# PMIC.net
KiCad netlist of a schematic drawn in Altium Designer
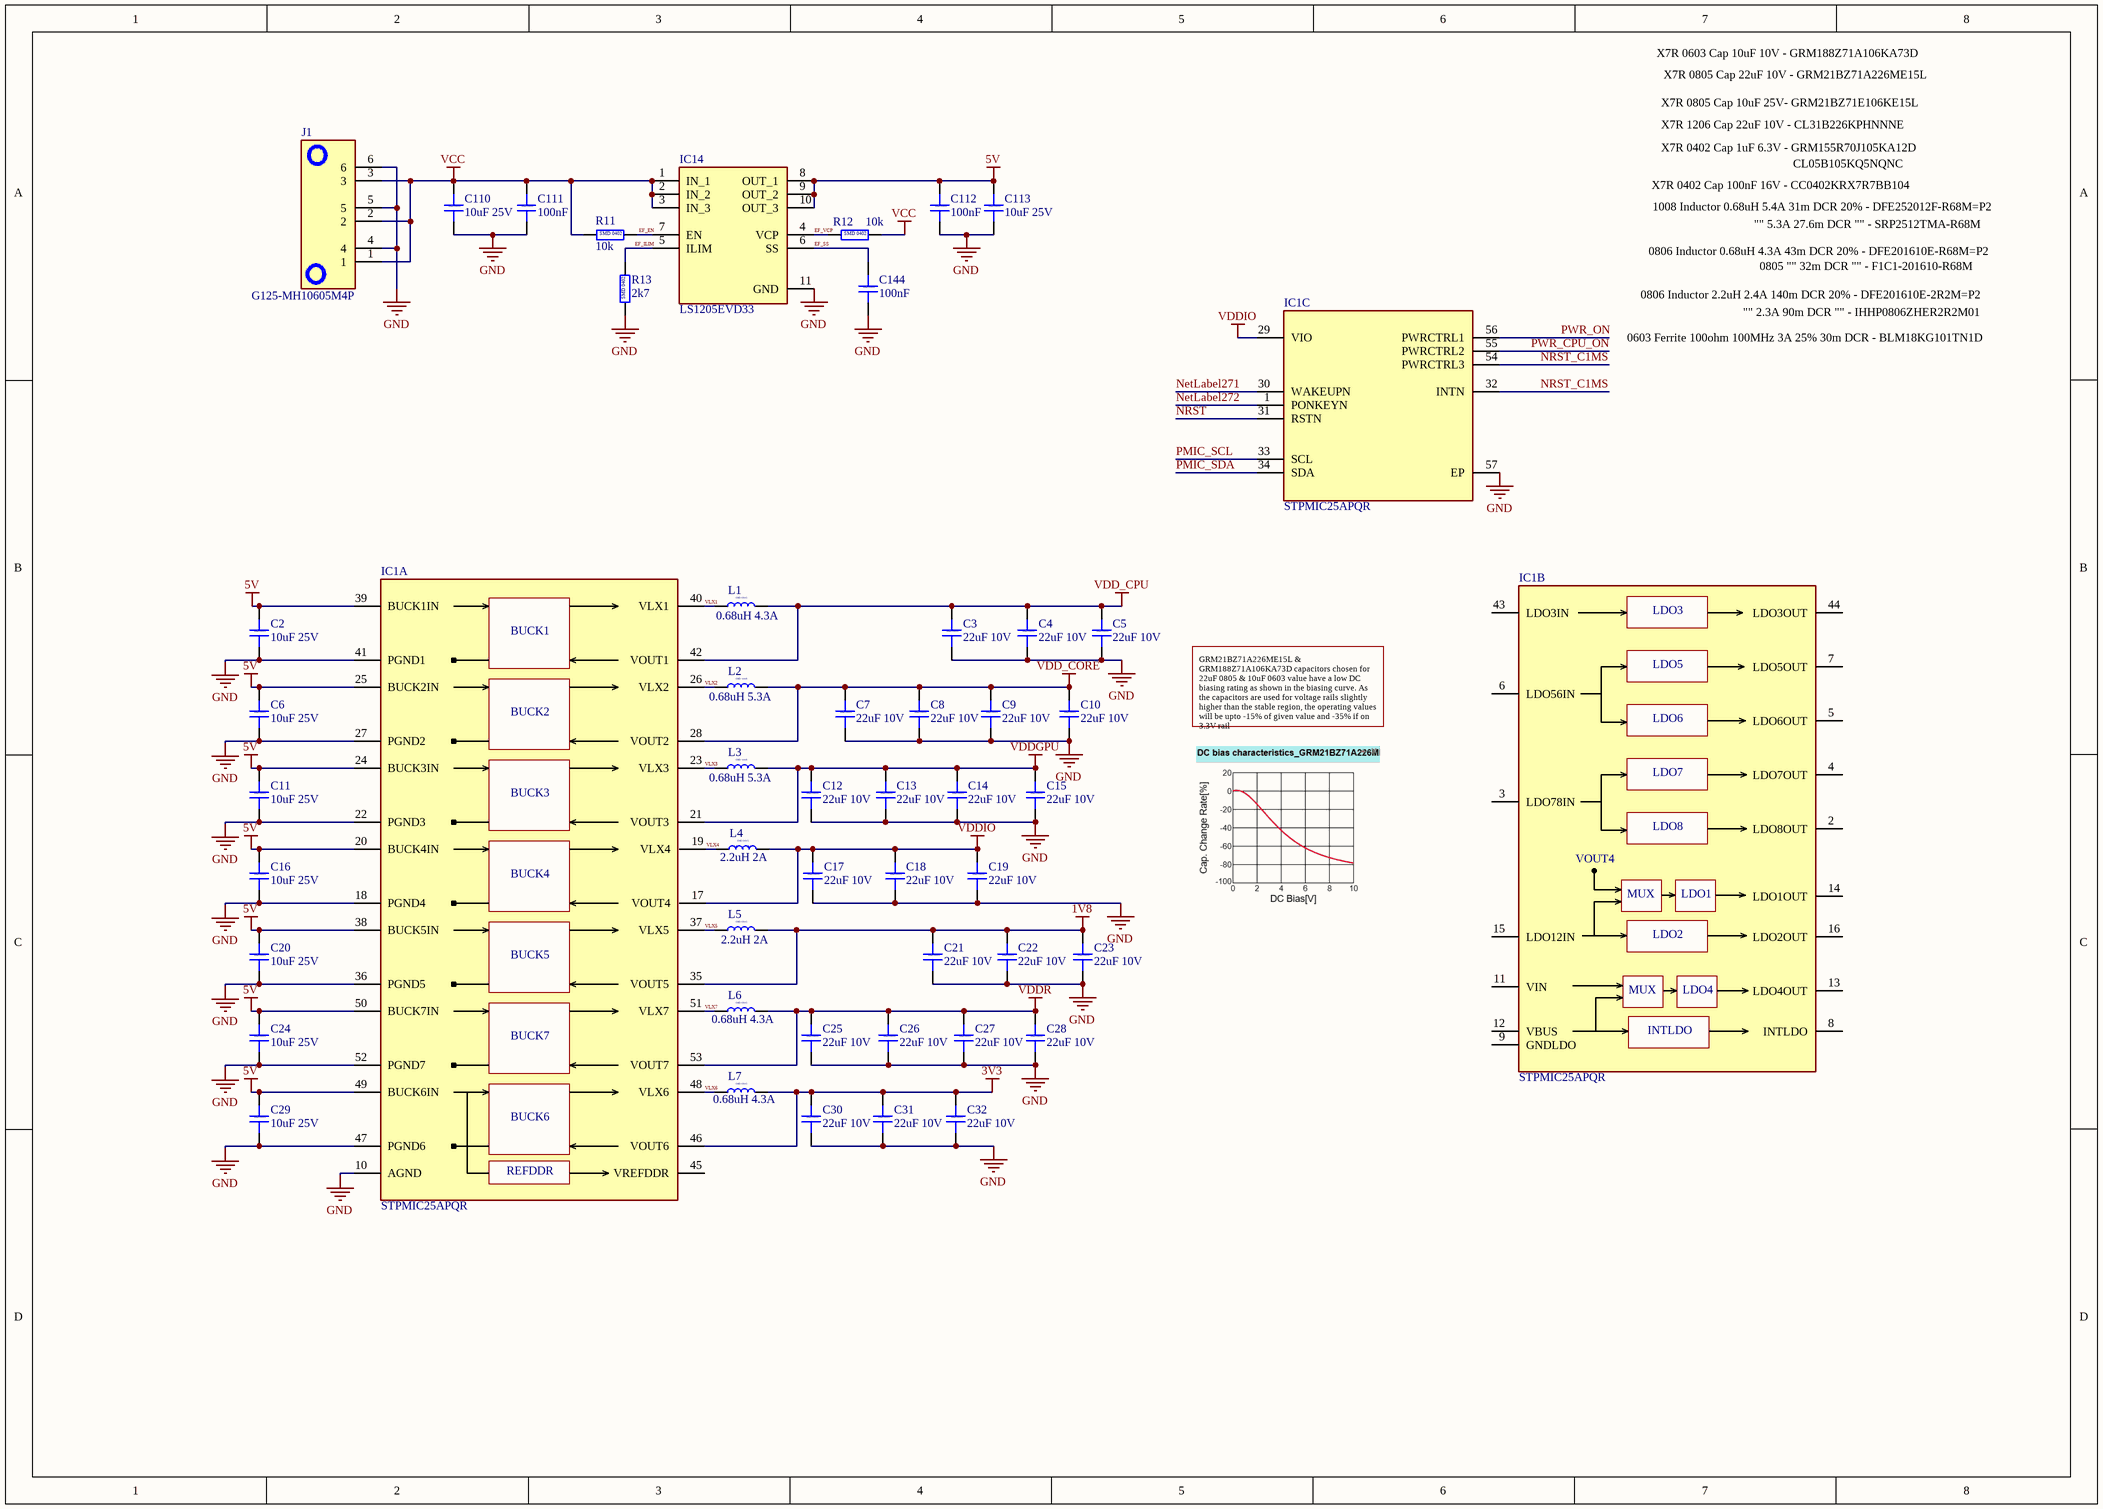
[diagram p0: PMIC.SchDoc]

(export (version "E")
  (design (tool "Eeschema 10.0.6"))
  (components
    (comp (ref "C2")
      (value "10uF 25V")
      (footprint "CAP_0805")
      (description "Capacitor SMD 0805 RATED")
      (libsource (lib "STeRG-Passives-Standard") (part "Capacitor-SMD-0805"))
    )
    (comp (ref "C3")
      (value "22uF 10V")
      (footprint "CAP_0805")
      (description "Capacitor SMD 0805 RATED")
      (libsource (lib "STeRG-Passives-Standard") (part "Capacitor-SMD-0805"))
    )
    (comp (ref "C4")
      (value "22uF 10V")
      (footprint "CAP_0805")
      (description "Capacitor SMD 0805 RATED")
      (libsource (lib "STeRG-Passives-Standard") (part "Capacitor-SMD-0805"))
    )
    (comp (ref "C5")
      (value "22uF 10V")
      (footprint "CAP_0805")
      (description "Capacitor SMD 0805 RATED")
      (libsource (lib "STeRG-Passives-Standard") (part "Capacitor-SMD-0805"))
    )
    (comp (ref "C6")
      (value "10uF 25V")
      (footprint "CAP_0805")
      (description "Capacitor SMD 0805 RATED")
      (libsource (lib "STeRG-Passives-Standard") (part "Capacitor-SMD-0805"))
    )
    (comp (ref "C7")
      (value "22uF 10V")
      (footprint "CAP_0805")
      (description "Capacitor SMD 0805 RATED")
      (libsource (lib "STeRG-Passives-Standard") (part "Capacitor-SMD-0805"))
    )
    (comp (ref "C8")
      (value "22uF 10V")
      (footprint "CAP_0805")
      (description "Capacitor SMD 0805 RATED")
      (libsource (lib "STeRG-Passives-Standard") (part "Capacitor-SMD-0805"))
    )
    (comp (ref "C9")
      (value "22uF 10V")
      (footprint "CAP_0805")
      (description "Capacitor SMD 0805 RATED")
      (libsource (lib "STeRG-Passives-Standard") (part "Capacitor-SMD-0805"))
    )
    (comp (ref "C10")
      (value "22uF 10V")
      (footprint "CAP_0805")
      (description "Capacitor SMD 0805 RATED")
      (libsource (lib "STeRG-Passives-Standard") (part "Capacitor-SMD-0805"))
    )
    (comp (ref "C11")
      (value "10uF 25V")
      (footprint "CAP_0805")
      (description "Capacitor SMD 0805 RATED")
      (libsource (lib "STeRG-Passives-Standard") (part "Capacitor-SMD-0805"))
    )
    (comp (ref "C12")
      (value "22uF 10V")
      (footprint "CAP_0805")
      (description "Capacitor SMD 0805 RATED")
      (libsource (lib "STeRG-Passives-Standard") (part "Capacitor-SMD-0805"))
    )
    (comp (ref "C13")
      (value "22uF 10V")
      (footprint "CAP_0805")
      (description "Capacitor SMD 0805 RATED")
      (libsource (lib "STeRG-Passives-Standard") (part "Capacitor-SMD-0805"))
    )
    (comp (ref "C14")
      (value "22uF 10V")
      (footprint "CAP_0805")
      (description "Capacitor SMD 0805 RATED")
      (libsource (lib "STeRG-Passives-Standard") (part "Capacitor-SMD-0805"))
    )
    (comp (ref "C15")
      (value "22uF 10V")
      (footprint "CAP_0805")
      (description "Capacitor SMD 0805 RATED")
      (libsource (lib "STeRG-Passives-Standard") (part "Capacitor-SMD-0805"))
    )
    (comp (ref "C16")
      (value "10uF 25V")
      (footprint "CAP_0805")
      (description "Capacitor SMD 0805 RATED")
      (libsource (lib "STeRG-Passives-Standard") (part "Capacitor-SMD-0805"))
    )
    (comp (ref "C17")
      (value "22uF 10V")
      (footprint "CAP_0805")
      (description "Capacitor SMD 0805 RATED")
      (libsource (lib "STeRG-Passives-Standard") (part "Capacitor-SMD-0805"))
    )
    (comp (ref "C18")
      (value "22uF 10V")
      (footprint "CAP_0805")
      (description "Capacitor SMD 0805 RATED")
      (libsource (lib "STeRG-Passives-Standard") (part "Capacitor-SMD-0805"))
    )
    (comp (ref "C19")
      (value "22uF 10V")
      (footprint "CAP_0805")
      (description "Capacitor SMD 0805 RATED")
      (libsource (lib "STeRG-Passives-Standard") (part "Capacitor-SMD-0805"))
    )
    (comp (ref "C20")
      (value "10uF 25V")
      (footprint "CAP_0805")
      (description "Capacitor SMD 0805 RATED")
      (libsource (lib "STeRG-Passives-Standard") (part "Capacitor-SMD-0805"))
    )
    (comp (ref "C21")
      (value "22uF 10V")
      (footprint "CAP_0805")
      (description "Capacitor SMD 0805 RATED")
      (libsource (lib "STeRG-Passives-Standard") (part "Capacitor-SMD-0805"))
    )
    (comp (ref "C22")
      (value "22uF 10V")
      (footprint "CAP_0805")
      (description "Capacitor SMD 0805 RATED")
      (libsource (lib "STeRG-Passives-Standard") (part "Capacitor-SMD-0805"))
    )
    (comp (ref "C23")
      (value "22uF 10V")
      (footprint "CAP_0805")
      (description "Capacitor SMD 0805 RATED")
      (libsource (lib "STeRG-Passives-Standard") (part "Capacitor-SMD-0805"))
    )
    (comp (ref "C24")
      (value "10uF 25V")
      (footprint "CAP_0805")
      (description "Capacitor SMD 0805 RATED")
      (libsource (lib "STeRG-Passives-Standard") (part "Capacitor-SMD-0805"))
    )
    (comp (ref "C25")
      (value "22uF 10V")
      (footprint "CAP_0805")
      (description "Capacitor SMD 0805 RATED")
      (libsource (lib "STeRG-Passives-Standard") (part "Capacitor-SMD-0805"))
    )
    (comp (ref "C26")
      (value "22uF 10V")
      (footprint "CAP_0805")
      (description "Capacitor SMD 0805 RATED")
      (libsource (lib "STeRG-Passives-Standard") (part "Capacitor-SMD-0805"))
    )
    (comp (ref "C27")
      (value "22uF 10V")
      (footprint "CAP_0805")
      (description "Capacitor SMD 0805 RATED")
      (libsource (lib "STeRG-Passives-Standard") (part "Capacitor-SMD-0805"))
    )
    (comp (ref "C28")
      (value "22uF 10V")
      (footprint "CAP_0805")
      (description "Capacitor SMD 0805 RATED")
      (libsource (lib "STeRG-Passives-Standard") (part "Capacitor-SMD-0805"))
    )
    (comp (ref "C29")
      (value "10uF 25V")
      (footprint "CAP_0805")
      (description "Capacitor SMD 0805 RATED")
      (libsource (lib "STeRG-Passives-Standard") (part "Capacitor-SMD-0805"))
    )
    (comp (ref "C30")
      (value "22uF 10V")
      (footprint "CAP_0805")
      (description "Capacitor SMD 0805 RATED")
      (libsource (lib "STeRG-Passives-Standard") (part "Capacitor-SMD-0805"))
    )
    (comp (ref "C31")
      (value "22uF 10V")
      (footprint "CAP_0805")
      (description "Capacitor SMD 0805 RATED")
      (libsource (lib "STeRG-Passives-Standard") (part "Capacitor-SMD-0805"))
    )
    (comp (ref "C32")
      (value "22uF 10V")
      (footprint "CAP_0805")
      (description "Capacitor SMD 0805 RATED")
      (libsource (lib "STeRG-Passives-Standard") (part "Capacitor-SMD-0805"))
    )
    (comp (ref "C110")
      (value "10uF 25V")
      (footprint "CAP_0805")
      (description "Capacitor SMD 0805 RATED")
      (libsource (lib "STeRG-Passives-Standard") (part "Capacitor-SMD-0805"))
    )
    (comp (ref "C111")
      (value "100nF")
      (footprint "CAP_0402")
      (description "Capacitor SMD 0402 RATED")
      (libsource (lib "STeRG-Passives-Standard") (part "Capacitor-SMD-0402"))
    )
    (comp (ref "C112")
      (value "100nF")
      (footprint "CAP_0402")
      (description "Capacitor SMD 0402 RATED")
      (libsource (lib "STeRG-Passives-Standard") (part "Capacitor-SMD-0402"))
    )
    (comp (ref "C113")
      (value "10uF 25V")
      (footprint "CAP_0805")
      (description "Capacitor SMD 0805 RATED")
      (libsource (lib "STeRG-Passives-Standard") (part "Capacitor-SMD-0805"))
    )
    (comp (ref "C144")
      (value "100nF")
      (footprint "CAP_0402")
      (description "Capacitor SMD 0402 RATED")
      (libsource (lib "STeRG-Passives-Standard") (part "Capacitor-SMD-0402"))
    )
    (comp (ref "IC1")
      (value "STPMIC25APQR")
      (footprint "QFN40P650X650X90-57N-D")
      (description "Integrated Circuit")
      (fields (field (name "MOUSER PART NUMBER") "511-STPMIC25APQR"))
      (libsource (lib "STeRG-ICs-Standard") (part "STPMIC25APQR"))
    )
    (comp (ref "IC14")
      (value "LS1205EVD33")
      (footprint "SamacSys:LS1205EVD33")
      (description "Integrated Circuit")
      (fields (field (name "MOUSER PART NUMBER") "576-LS1205EVD33"))
      (libsource (lib "STeRG-Passives-Standard") (part "LS1205EVD33"))
    )
    (comp (ref "J1")
      (value "G125-MH10605M4P")
      (footprint "G125-MH10605M4P_1")
      (description "Connector")
      (fields (field (name "MOUSER PART NUMBER") "855-G125MH1065M4PM4P"))
      (libsource (lib "STeRG-Passives-Standard") (part "G125-MH10605M4P"))
    )
    (comp (ref "L1")
      (value "0.68uH 4.3A")
      (footprint "DFE2HCAH1R0MJ0L")
      (description "Inductor SMD 0805")
      (libsource (lib "STeRG-Passives-Standard") (part "Inductor-SMD-RF-0806/0805"))
    )
    (comp (ref "L2")
      (value "0.68uH 5.3A")
      (footprint "1285ASH1R0MP2")
      (description "Inductor SMD 1008")
      (libsource (lib "STeRG-Passives-Standard") (part "Inductor-SMD-RF-1008"))
    )
    (comp (ref "L3")
      (value "0.68uH 5.3A")
      (footprint "1285ASH1R0MP2")
      (description "Inductor SMD 1008")
      (libsource (lib "STeRG-Passives-Standard") (part "Inductor-SMD-RF-1008"))
    )
    (comp (ref "L4")
      (value "2.2uH 2A")
      (footprint "DFE2HCAH1R0MJ0L")
      (description "Inductor SMD 0805")
      (libsource (lib "STeRG-Passives-Standard") (part "Inductor-SMD-RF-0806/0805"))
    )
    (comp (ref "L5")
      (value "2.2uH 2A")
      (footprint "DFE2HCAH1R0MJ0L")
      (description "Inductor SMD 0805")
      (libsource (lib "STeRG-Passives-Standard") (part "Inductor-SMD-RF-0806/0805"))
    )
    (comp (ref "L6")
      (value "0.68uH 4.3A")
      (footprint "DFE2HCAH1R0MJ0L")
      (description "Inductor SMD 0805")
      (libsource (lib "STeRG-Passives-Standard") (part "Inductor-SMD-RF-0806/0805"))
    )
    (comp (ref "L7")
      (value "0.68uH 4.3A")
      (footprint "DFE2HCAH1R0MJ0L")
      (description "Inductor SMD 0805")
      (libsource (lib "STeRG-Passives-Standard") (part "Inductor-SMD-RF-0806/0805"))
    )
    (comp (ref "R11")
      (value "10k")
      (footprint "RES_0402")
      (description "Resistor SMD 0402 RATED")
      (libsource (lib "STeRG-Passives-Standard") (part "Resistor-SMD-0402"))
    )
    (comp (ref "R12")
      (value "10k")
      (footprint "RES_0402")
      (description "Resistor SMD 0402 RATED")
      (libsource (lib "STeRG-Passives-Standard") (part "Resistor-SMD-0402"))
    )
    (comp (ref "R13")
      (value "2k7")
      (footprint "RES_0402")
      (description "Resistor SMD 0402 RATED")
      (libsource (lib "STeRG-Passives-Standard") (part "Resistor-SMD-0402"))
    )
  )
  (nets
    (net (code "1") (name "/EF_EN") (class "Default")
      (node (ref "IC14") (pin "7") (pinfunction "EN_7") (pintype "passive"))
      (node (ref "R11") (pin "2") (pinfunction "2_2") (pintype "passive"))
    )
    (net (code "2") (name "/EF_ILIM") (class "Default")
      (node (ref "IC14") (pin "5") (pinfunction "ILIM_5") (pintype "passive"))
      (node (ref "R13") (pin "2") (pinfunction "2_2") (pintype "passive"))
    )
    (net (code "3") (name "/EF_SS") (class "Default")
      (node (ref "C144") (pin "1") (pinfunction "1_1") (pintype "passive"))
      (node (ref "IC14") (pin "6") (pinfunction "SS_6") (pintype "passive"))
    )
    (net (code "4") (name "/EF_VCP") (class "Default")
      (node (ref "IC14") (pin "4") (pinfunction "VCP_4") (pintype "passive"))
      (node (ref "R12") (pin "1") (pinfunction "1_1") (pintype "passive"))
    )
    (net (code "5") (name "/NRST") (class "Default")
      (node (ref "IC1") (pin "31") (pinfunction "RSTN_31") (pintype "passive"))
    )
    (net (code "6") (name "/NRST_C1MS") (class "Default")
      (node (ref "IC1") (pin "32") (pinfunction "INTN_32") (pintype "passive"))
      (node (ref "IC1") (pin "54") (pinfunction "PWRCTRL3_54") (pintype "passive"))
    )
    (net (code "7") (name "/NetLabel271") (class "Default")
      (node (ref "IC1") (pin "30") (pinfunction "WAKEUPN_30") (pintype "passive"))
    )
    (net (code "8") (name "/NetLabel272") (class "Default")
      (node (ref "IC1") (pin "1") (pinfunction "PONKEYN_1") (pintype "passive"))
    )
    (net (code "9") (name "/PMIC_SCL") (class "Default")
      (node (ref "IC1") (pin "33") (pinfunction "SCL_33") (pintype "passive"))
    )
    (net (code "10") (name "/PMIC_SDA") (class "Default")
      (node (ref "IC1") (pin "34") (pinfunction "SDA_34") (pintype "passive"))
    )
    (net (code "11") (name "/PWR_CPU_ON") (class "Default")
      (node (ref "IC1") (pin "55") (pinfunction "PWRCTRL2_55") (pintype "passive"))
    )
    (net (code "12") (name "/PWR_ON") (class "Default")
      (node (ref "IC1") (pin "56") (pinfunction "PWRCTRL1_56") (pintype "passive"))
    )
    (net (code "13") (name "/VLX1") (class "Default")
      (node (ref "IC1") (pin "40") (pinfunction "VLX1_40") (pintype "passive"))
      (node (ref "L1") (pin "1") (pinfunction "1_1") (pintype "passive"))
    )
    (net (code "14") (name "/VLX2") (class "Default")
      (node (ref "IC1") (pin "26") (pinfunction "VLX2_26") (pintype "passive"))
      (node (ref "L2") (pin "1") (pinfunction "1_1") (pintype "passive"))
    )
    (net (code "15") (name "/VLX3") (class "Default")
      (node (ref "IC1") (pin "23") (pinfunction "VLX3_23") (pintype "passive"))
      (node (ref "L3") (pin "1") (pinfunction "1_1") (pintype "passive"))
    )
    (net (code "16") (name "/VLX4") (class "Default")
      (node (ref "IC1") (pin "19") (pinfunction "VLX4_19") (pintype "passive"))
      (node (ref "L4") (pin "1") (pinfunction "1_1") (pintype "passive"))
    )
    (net (code "17") (name "/VLX5") (class "Default")
      (node (ref "IC1") (pin "37") (pinfunction "VLX5_37") (pintype "passive"))
      (node (ref "L5") (pin "1") (pinfunction "1_1") (pintype "passive"))
    )
    (net (code "18") (name "/VLX6") (class "Default")
      (node (ref "IC1") (pin "48") (pinfunction "VLX6_48") (pintype "passive"))
      (node (ref "L7") (pin "1") (pinfunction "1_1") (pintype "passive"))
    )
    (net (code "19") (name "/VLX7") (class "Default")
      (node (ref "IC1") (pin "51") (pinfunction "VLX7_51") (pintype "passive"))
      (node (ref "L6") (pin "1") (pinfunction "1_1") (pintype "passive"))
    )
    (net (code "20") (name "1V8") (class "Default")
      (node (ref "C21") (pin "1") (pinfunction "1_1") (pintype "passive"))
      (node (ref "C22") (pin "1") (pinfunction "1_1") (pintype "passive"))
      (node (ref "C23") (pin "1") (pinfunction "1_1") (pintype "passive"))
      (node (ref "IC1") (pin "35") (pinfunction "VOUT5_35") (pintype "passive"))
      (node (ref "L5") (pin "2") (pinfunction "2_2") (pintype "passive"))
    )
    (net (code "21") (name "3V3") (class "Default")
      (node (ref "C30") (pin "1") (pinfunction "1_1") (pintype "passive"))
      (node (ref "C31") (pin "1") (pinfunction "1_1") (pintype "passive"))
      (node (ref "C32") (pin "1") (pinfunction "1_1") (pintype "passive"))
      (node (ref "IC1") (pin "46") (pinfunction "VOUT6_46") (pintype "passive"))
      (node (ref "L7") (pin "2") (pinfunction "2_2") (pintype "passive"))
    )
    (net (code "22") (name "5V") (class "Default")
      (node (ref "C11") (pin "1") (pinfunction "1_1") (pintype "passive"))
      (node (ref "C112") (pin "1") (pinfunction "1_1") (pintype "passive"))
      (node (ref "C113") (pin "1") (pinfunction "1_1") (pintype "passive"))
      (node (ref "C16") (pin "1") (pinfunction "1_1") (pintype "passive"))
      (node (ref "C2") (pin "1") (pinfunction "1_1") (pintype "passive"))
      (node (ref "C20") (pin "1") (pinfunction "1_1") (pintype "passive"))
      (node (ref "C24") (pin "1") (pinfunction "1_1") (pintype "passive"))
      (node (ref "C29") (pin "1") (pinfunction "1_1") (pintype "passive"))
      (node (ref "C6") (pin "1") (pinfunction "1_1") (pintype "passive"))
      (node (ref "IC1") (pin "20") (pinfunction "BUCK4IN_20") (pintype "passive"))
      (node (ref "IC1") (pin "24") (pinfunction "BUCK3IN_24") (pintype "passive"))
      (node (ref "IC1") (pin "25") (pinfunction "BUCK2IN_25") (pintype "passive"))
      (node (ref "IC1") (pin "38") (pinfunction "BUCK5IN_38") (pintype "passive"))
      (node (ref "IC1") (pin "39") (pinfunction "BUCK1IN_39") (pintype "passive"))
      (node (ref "IC1") (pin "49") (pinfunction "BUCK6IN_49") (pintype "passive"))
      (node (ref "IC1") (pin "50") (pinfunction "BUCK7IN_50") (pintype "passive"))
      (node (ref "IC14") (pin "10") (pinfunction "OUT_3_10") (pintype "passive"))
      (node (ref "IC14") (pin "8") (pinfunction "OUT_1_8") (pintype "passive"))
      (node (ref "IC14") (pin "9") (pinfunction "OUT_2_9") (pintype "passive"))
    )
    (net (code "23") (name "GND") (class "Default")
      (node (ref "C10") (pin "2") (pinfunction "2_2") (pintype "passive"))
      (node (ref "C11") (pin "2") (pinfunction "2_2") (pintype "passive"))
      (node (ref "C110") (pin "2") (pinfunction "2_2") (pintype "passive"))
      (node (ref "C111") (pin "2") (pinfunction "2_2") (pintype "passive"))
      (node (ref "C112") (pin "2") (pinfunction "2_2") (pintype "passive"))
      (node (ref "C113") (pin "2") (pinfunction "2_2") (pintype "passive"))
      (node (ref "C12") (pin "2") (pinfunction "2_2") (pintype "passive"))
      (node (ref "C13") (pin "2") (pinfunction "2_2") (pintype "passive"))
      (node (ref "C14") (pin "2") (pinfunction "2_2") (pintype "passive"))
      (node (ref "C144") (pin "2") (pinfunction "2_2") (pintype "passive"))
      (node (ref "C15") (pin "2") (pinfunction "2_2") (pintype "passive"))
      (node (ref "C16") (pin "2") (pinfunction "2_2") (pintype "passive"))
      (node (ref "C17") (pin "2") (pinfunction "2_2") (pintype "passive"))
      (node (ref "C18") (pin "2") (pinfunction "2_2") (pintype "passive"))
      (node (ref "C19") (pin "2") (pinfunction "2_2") (pintype "passive"))
      (node (ref "C2") (pin "2") (pinfunction "2_2") (pintype "passive"))
      (node (ref "C20") (pin "2") (pinfunction "2_2") (pintype "passive"))
      (node (ref "C21") (pin "2") (pinfunction "2_2") (pintype "passive"))
      (node (ref "C22") (pin "2") (pinfunction "2_2") (pintype "passive"))
      (node (ref "C23") (pin "2") (pinfunction "2_2") (pintype "passive"))
      (node (ref "C24") (pin "2") (pinfunction "2_2") (pintype "passive"))
      (node (ref "C25") (pin "2") (pinfunction "2_2") (pintype "passive"))
      (node (ref "C26") (pin "2") (pinfunction "2_2") (pintype "passive"))
      (node (ref "C27") (pin "2") (pinfunction "2_2") (pintype "passive"))
      (node (ref "C28") (pin "2") (pinfunction "2_2") (pintype "passive"))
      (node (ref "C29") (pin "2") (pinfunction "2_2") (pintype "passive"))
      (node (ref "C3") (pin "2") (pinfunction "2_2") (pintype "passive"))
      (node (ref "C30") (pin "2") (pinfunction "2_2") (pintype "passive"))
      (node (ref "C31") (pin "2") (pinfunction "2_2") (pintype "passive"))
      (node (ref "C32") (pin "2") (pinfunction "2_2") (pintype "passive"))
      (node (ref "C4") (pin "2") (pinfunction "2_2") (pintype "passive"))
      (node (ref "C5") (pin "2") (pinfunction "2_2") (pintype "passive"))
      (node (ref "C6") (pin "2") (pinfunction "2_2") (pintype "passive"))
      (node (ref "C7") (pin "2") (pinfunction "2_2") (pintype "passive"))
      (node (ref "C8") (pin "2") (pinfunction "2_2") (pintype "passive"))
      (node (ref "C9") (pin "2") (pinfunction "2_2") (pintype "passive"))
      (node (ref "IC1") (pin "10") (pinfunction "AGND_10") (pintype "passive"))
      (node (ref "IC1") (pin "18") (pinfunction "PGND4_18") (pintype "passive"))
      (node (ref "IC1") (pin "22") (pinfunction "PGND3_22") (pintype "passive"))
      (node (ref "IC1") (pin "27") (pinfunction "PGND2_27") (pintype "passive"))
      (node (ref "IC1") (pin "36") (pinfunction "PGND5_36") (pintype "passive"))
      (node (ref "IC1") (pin "41") (pinfunction "PGND1_41") (pintype "passive"))
      (node (ref "IC1") (pin "47") (pinfunction "PGND6_47") (pintype "passive"))
      (node (ref "IC1") (pin "52") (pinfunction "PGND7_52") (pintype "passive"))
      (node (ref "IC1") (pin "57") (pinfunction "EP_57") (pintype "passive"))
      (node (ref "IC14") (pin "11") (pinfunction "GND_11") (pintype "passive"))
      (node (ref "J1") (pin "4") (pinfunction "4_4") (pintype "passive"))
      (node (ref "J1") (pin "5") (pinfunction "5_5") (pintype "passive"))
      (node (ref "J1") (pin "6") (pinfunction "6_6") (pintype "passive"))
      (node (ref "R13") (pin "1") (pinfunction "1_1") (pintype "passive"))
    )
    (net (code "24") (name "VCC") (class "Default")
      (node (ref "C110") (pin "1") (pinfunction "1_1") (pintype "passive"))
      (node (ref "C111") (pin "1") (pinfunction "1_1") (pintype "passive"))
      (node (ref "IC14") (pin "1") (pinfunction "IN_1_1") (pintype "passive"))
      (node (ref "IC14") (pin "2") (pinfunction "IN_2_2") (pintype "passive"))
      (node (ref "IC14") (pin "3") (pinfunction "IN_3_3") (pintype "passive"))
      (node (ref "J1") (pin "1") (pinfunction "1_1") (pintype "passive"))
      (node (ref "J1") (pin "2") (pinfunction "2_2") (pintype "passive"))
      (node (ref "J1") (pin "3") (pinfunction "3_3") (pintype "passive"))
      (node (ref "R11") (pin "1") (pinfunction "1_1") (pintype "passive"))
      (node (ref "R12") (pin "2") (pinfunction "2_2") (pintype "passive"))
    )
    (net (code "25") (name "VDDGPU") (class "Default")
      (node (ref "C12") (pin "1") (pinfunction "1_1") (pintype "passive"))
      (node (ref "C13") (pin "1") (pinfunction "1_1") (pintype "passive"))
      (node (ref "C14") (pin "1") (pinfunction "1_1") (pintype "passive"))
      (node (ref "C15") (pin "1") (pinfunction "1_1") (pintype "passive"))
      (node (ref "IC1") (pin "21") (pinfunction "VOUT3_21") (pintype "passive"))
      (node (ref "L3") (pin "2") (pinfunction "2_2") (pintype "passive"))
    )
    (net (code "26") (name "VDDIO") (class "Default")
      (node (ref "C17") (pin "1") (pinfunction "1_1") (pintype "passive"))
      (node (ref "C18") (pin "1") (pinfunction "1_1") (pintype "passive"))
      (node (ref "C19") (pin "1") (pinfunction "1_1") (pintype "passive"))
      (node (ref "IC1") (pin "17") (pinfunction "VOUT4_17") (pintype "passive"))
      (node (ref "IC1") (pin "29") (pinfunction "VIO_29") (pintype "passive"))
      (node (ref "L4") (pin "2") (pinfunction "2_2") (pintype "passive"))
    )
    (net (code "27") (name "VDDR") (class "Default")
      (node (ref "C25") (pin "1") (pinfunction "1_1") (pintype "passive"))
      (node (ref "C26") (pin "1") (pinfunction "1_1") (pintype "passive"))
      (node (ref "C27") (pin "1") (pinfunction "1_1") (pintype "passive"))
      (node (ref "C28") (pin "1") (pinfunction "1_1") (pintype "passive"))
      (node (ref "IC1") (pin "53") (pinfunction "VOUT7_53") (pintype "passive"))
      (node (ref "L6") (pin "2") (pinfunction "2_2") (pintype "passive"))
    )
    (net (code "28") (name "VDD_CORE") (class "Default")
      (node (ref "C10") (pin "1") (pinfunction "1_1") (pintype "passive"))
      (node (ref "C7") (pin "1") (pinfunction "1_1") (pintype "passive"))
      (node (ref "C8") (pin "1") (pinfunction "1_1") (pintype "passive"))
      (node (ref "C9") (pin "1") (pinfunction "1_1") (pintype "passive"))
      (node (ref "IC1") (pin "28") (pinfunction "VOUT2_28") (pintype "passive"))
      (node (ref "L2") (pin "2") (pinfunction "2_2") (pintype "passive"))
    )
    (net (code "29") (name "VDD_CPU") (class "Default")
      (node (ref "C3") (pin "1") (pinfunction "1_1") (pintype "passive"))
      (node (ref "C4") (pin "1") (pinfunction "1_1") (pintype "passive"))
      (node (ref "C5") (pin "1") (pinfunction "1_1") (pintype "passive"))
      (node (ref "IC1") (pin "42") (pinfunction "VOUT1_42") (pintype "passive"))
      (node (ref "L1") (pin "2") (pinfunction "2_2") (pintype "passive"))
    )
    (net (code "30") (name "unconnected-(IC1A-VREFDDR-Pad45)") (class "Default")
      (node (ref "IC1") (pin "45") (pinfunction "VREFDDR_45") (pintype "passive"))
    )
    (net (code "31") (name "unconnected-(IC1B-GNDLDO-Pad9)") (class "Default")
      (node (ref "IC1") (pin "9") (pinfunction "GNDLDO_9") (pintype "passive"))
    )
    (net (code "32") (name "unconnected-(IC1B-INTLDO-Pad8)") (class "Default")
      (node (ref "IC1") (pin "8") (pinfunction "INTLDO_8") (pintype "passive"))
    )
    (net (code "33") (name "unconnected-(IC1B-LDO1OUT-Pad14)") (class "Default")
      (node (ref "IC1") (pin "14") (pinfunction "LDO1OUT_14") (pintype "passive"))
    )
    (net (code "34") (name "unconnected-(IC1B-LDO2OUT-Pad16)") (class "Default")
      (node (ref "IC1") (pin "16") (pinfunction "LDO2OUT_16") (pintype "passive"))
    )
    (net (code "35") (name "unconnected-(IC1B-LDO3IN-Pad43)") (class "Default")
      (node (ref "IC1") (pin "43") (pinfunction "LDO3IN_43") (pintype "passive"))
    )
    (net (code "36") (name "unconnected-(IC1B-LDO3OUT-Pad44)") (class "Default")
      (node (ref "IC1") (pin "44") (pinfunction "LDO3OUT_44") (pintype "passive"))
    )
    (net (code "37") (name "unconnected-(IC1B-LDO4OUT-Pad13)") (class "Default")
      (node (ref "IC1") (pin "13") (pinfunction "LDO4OUT_13") (pintype "passive"))
    )
    (net (code "38") (name "unconnected-(IC1B-LDO5OUT-Pad7)") (class "Default")
      (node (ref "IC1") (pin "7") (pinfunction "LDO5OUT_7") (pintype "passive"))
    )
    (net (code "39") (name "unconnected-(IC1B-LDO6OUT-Pad5)") (class "Default")
      (node (ref "IC1") (pin "5") (pinfunction "LDO6OUT_5") (pintype "passive"))
    )
    (net (code "40") (name "unconnected-(IC1B-LDO7OUT-Pad4)") (class "Default")
      (node (ref "IC1") (pin "4") (pinfunction "LDO7OUT_4") (pintype "passive"))
    )
    (net (code "41") (name "unconnected-(IC1B-LDO8OUT-Pad2)") (class "Default")
      (node (ref "IC1") (pin "2") (pinfunction "LDO8OUT_2") (pintype "passive"))
    )
    (net (code "42") (name "unconnected-(IC1B-LDO12IN-Pad15)") (class "Default")
      (node (ref "IC1") (pin "15") (pinfunction "LDO12IN_15") (pintype "passive"))
    )
    (net (code "43") (name "unconnected-(IC1B-LDO56IN-Pad6)") (class "Default")
      (node (ref "IC1") (pin "6") (pinfunction "LDO56IN_6") (pintype "passive"))
    )
    (net (code "44") (name "unconnected-(IC1B-LDO78IN-Pad3)") (class "Default")
      (node (ref "IC1") (pin "3") (pinfunction "LDO78IN_3") (pintype "passive"))
    )
    (net (code "45") (name "unconnected-(IC1B-VBUS-Pad12)") (class "Default")
      (node (ref "IC1") (pin "12") (pinfunction "VBUS_12") (pintype "passive"))
    )
    (net (code "46") (name "unconnected-(IC1B-VIN-Pad11)") (class "Default")
      (node (ref "IC1") (pin "11") (pinfunction "VIN_11") (pintype "passive"))
    )
  )
)
